# xv11_lidar_controller.net
KiCad netlist of a schematic drawn in EAGLE
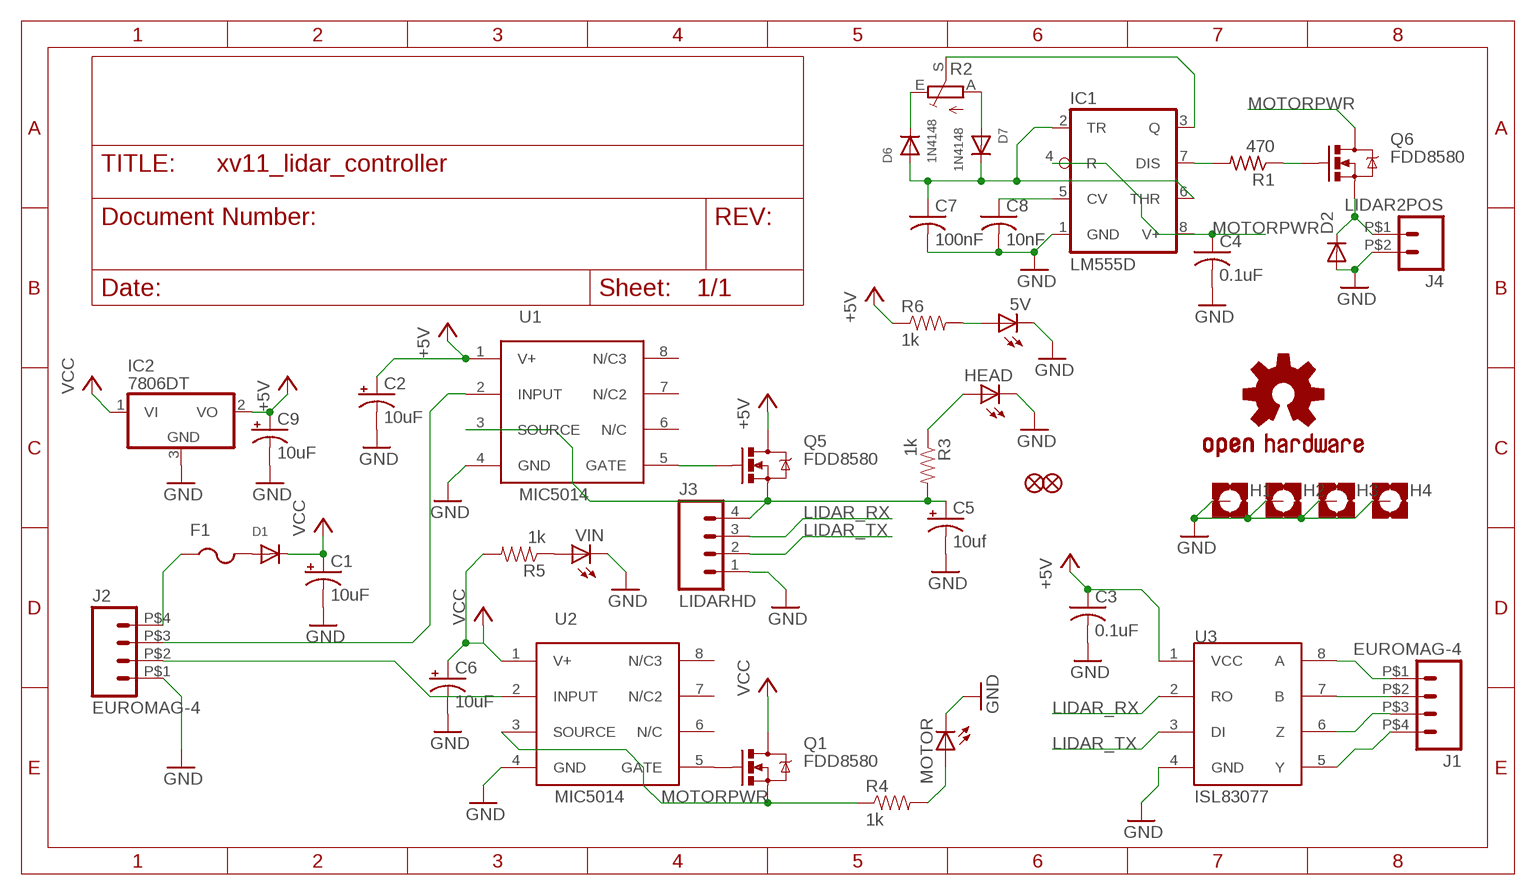
[diagram p0: schematic, sheet 1]

(export (version "E")
  (design (tool "Eeschema 10.0.6"))
  (components
    (comp (ref "5V")
      (value "LEDCHIP-LED0805")
      (footprint "eagle-import:CHIP-LED0805")
      (libsource (lib "eagle-import") (part "LEDCHIP-LED0805"))
    )
    (comp (ref "C1")
      (value "10uF")
      (footprint "eagle-import:CT6032")
      (libsource (lib "eagle-import") (part "CPOL-USCT6032"))
    )
    (comp (ref "C2")
      (value "10uF")
      (footprint "eagle-import:CT6032")
      (libsource (lib "eagle-import") (part "CPOL-USCT6032"))
    )
    (comp (ref "C3")
      (value "0.1uF")
      (footprint "eagle-import:C0805")
      (libsource (lib "eagle-import") (part "C-USC0805"))
    )
    (comp (ref "C4")
      (value "0.1uF")
      (footprint "eagle-import:C0805")
      (libsource (lib "eagle-import") (part "C-USC0805"))
    )
    (comp (ref "C5")
      (value "10uf")
      (footprint "eagle-import:CT6032")
      (libsource (lib "eagle-import") (part "CPOL-USCT6032"))
    )
    (comp (ref "C6")
      (value "10uF")
      (footprint "eagle-import:CT6032")
      (libsource (lib "eagle-import") (part "CPOL-USCT6032"))
    )
    (comp (ref "C7")
      (value "100nF")
      (footprint "eagle-import:C0805")
      (libsource (lib "eagle-import") (part "C-USC0805"))
    )
    (comp (ref "C8")
      (value "10nF")
      (footprint "eagle-import:C0805")
      (libsource (lib "eagle-import") (part "C-USC0805"))
    )
    (comp (ref "C9")
      (value "10uF")
      (footprint "eagle-import:CT6032")
      (libsource (lib "eagle-import") (part "CPOL-USCT6032"))
    )
    (comp (ref "D1")
      (value "DIODESMA")
      (footprint "eagle-import:SMADIODE")
      (libsource (lib "eagle-import") (part "adafruit_DIODESMA"))
    )
    (comp (ref "D2")
      (value "DIODESMA")
      (footprint "eagle-import:SMA-DIODE")
      (libsource (lib "eagle-import") (part "DIODESMA"))
    )
    (comp (ref "D6")
      (value "1N4148")
      (footprint "eagle-import:SOD-323F")
      (libsource (lib "eagle-import") (part "DIODESOD-323F"))
    )
    (comp (ref "D7")
      (value "1N4148")
      (footprint "eagle-import:SOD-323F")
      (libsource (lib "eagle-import") (part "DIODESOD-323F"))
    )
    (comp (ref "F1")
      (value "PTCFUSE-1812")
      (footprint "eagle-import:1812")
      (libsource (lib "eagle-import") (part "PTCFUSE-1812"))
    )
    (comp (ref "H1")
      (value "MOUNT-PAD-SQUARE5.5")
      (footprint "eagle-import:5,5-PAD-SQUARE")
      (libsource (lib "eagle-import") (part "MOUNT-PAD-SQUARE5.5"))
    )
    (comp (ref "H2")
      (value "MOUNT-PAD-SQUARE5.5")
      (footprint "eagle-import:5,5-PAD-SQUARE")
      (libsource (lib "eagle-import") (part "MOUNT-PAD-SQUARE5.5"))
    )
    (comp (ref "H3")
      (value "MOUNT-PAD-SQUARE5.5")
      (footprint "eagle-import:5,5-PAD-SQUARE")
      (libsource (lib "eagle-import") (part "MOUNT-PAD-SQUARE5.5"))
    )
    (comp (ref "H4")
      (value "MOUNT-PAD-SQUARE5.5")
      (footprint "eagle-import:5,5-PAD-SQUARE")
      (libsource (lib "eagle-import") (part "MOUNT-PAD-SQUARE5.5"))
    )
    (comp (ref "HEAD")
      (value "LEDCHIP-LED0805")
      (footprint "eagle-import:CHIP-LED0805")
      (libsource (lib "eagle-import") (part "LEDCHIP-LED0805"))
    )
    (comp (ref "IC1")
      (value "LM555D")
      (footprint "eagle-import:SO08")
      (libsource (lib "eagle-import") (part "555DLM"))
    )
    (comp (ref "IC2")
      (value "7806DT")
      (footprint "eagle-import:TO252")
      (libsource (lib "eagle-import") (part "78DT06"))
    )
    (comp (ref "J1")
      (value "EUROMAG-4")
      (footprint "eagle-import:M4")
      (libsource (lib "eagle-import") (part "EUROMAG-4"))
    )
    (comp (ref "J2")
      (value "EUROMAG-4")
      (footprint "eagle-import:M4")
      (libsource (lib "eagle-import") (part "EUROMAG-4"))
    )
    (comp (ref "J3")
      (value "LIDARHD")
      (footprint "eagle-import:2MM4POS")
      (libsource (lib "eagle-import") (part "LIDAR4POS"))
    )
    (comp (ref "J4")
      (value "LIDAR2POS")
      (footprint "eagle-import:2MM2POS")
      (libsource (lib "eagle-import") (part "LIDAR2POS"))
    )
    (comp (ref "JP1")
      (value "FIDUCIAL1.5X3")
      (footprint "eagle-import:FIDUCIAL-1.5X3")
      (libsource (lib "eagle-import") (part "FIDUCIAL1.5X3"))
    )
    (comp (ref "JP2")
      (value "FIDUCIAL1.5X3")
      (footprint "eagle-import:FIDUCIAL-1.5X3")
      (libsource (lib "eagle-import") (part "FIDUCIAL1.5X3"))
    )
    (comp (ref "MOTOR")
      (value "LEDCHIP-LED0805")
      (footprint "eagle-import:CHIP-LED0805")
      (libsource (lib "eagle-import") (part "LEDCHIP-LED0805"))
    )
    (comp (ref "Q1")
      (value "FDD8580")
      (footprint "eagle-import:DPAK")
      (libsource (lib "eagle-import") (part "MOSFET-NCHANNELFDD8580"))
    )
    (comp (ref "Q5")
      (value "FDD8580")
      (footprint "eagle-import:DPAK")
      (libsource (lib "eagle-import") (part "MOSFET-NCHANNELFDD8580"))
    )
    (comp (ref "Q6")
      (value "FDD8580")
      (footprint "eagle-import:DPAK")
      (libsource (lib "eagle-import") (part "MOSFET-NCHANNELFDD8580"))
    )
    (comp (ref "R1")
      (value "470")
      (footprint "eagle-import:R0805")
      (libsource (lib "eagle-import") (part "R-US_R0805"))
    )
    (comp (ref "R2")
      (value "TRIM_EU-B25P")
      (footprint "eagle-import:B25P")
      (libsource (lib "eagle-import") (part "TRIM_EU-B25P"))
    )
    (comp (ref "R3")
      (value "1k")
      (footprint "eagle-import:0805")
      (libsource (lib "eagle-import") (part "RESISTOR0805-RES"))
    )
    (comp (ref "R4")
      (value "1k")
      (footprint "eagle-import:0805")
      (libsource (lib "eagle-import") (part "RESISTOR0805-RES"))
    )
    (comp (ref "R5")
      (value "1k")
      (footprint "eagle-import:0805")
      (libsource (lib "eagle-import") (part "RESISTOR0805-RES"))
    )
    (comp (ref "R6")
      (value "1k")
      (footprint "eagle-import:0805")
      (libsource (lib "eagle-import") (part "RESISTOR0805-RES"))
    )
    (comp (ref "U$2")
      (value "OSHW-LOGOL")
      (footprint "eagle-import:OSHW-LOGO-L")
      (libsource (lib "eagle-import") (part "OSHW-LOGOL"))
    )
    (comp (ref "U1")
      (value "MIC5014")
      (footprint "eagle-import:SO08")
      (libsource (lib "eagle-import") (part "MIC5014"))
    )
    (comp (ref "U2")
      (value "MIC5014")
      (footprint "eagle-import:SO08")
      (libsource (lib "eagle-import") (part "MIC5014"))
    )
    (comp (ref "U3")
      (value "ISL83077")
      (footprint "eagle-import:SO08")
      (libsource (lib "eagle-import") (part "ISL83077"))
    )
    (comp (ref "VIN")
      (value "LEDCHIP-LED0805")
      (footprint "eagle-import:CHIP-LED0805")
      (libsource (lib "eagle-import") (part "LEDCHIP-LED0805"))
    )
  )
  (nets
    (net (code "1") (name "+5V") (class "Default")
      (node (ref "C2") (pin "+") (pinfunction "+_+") (pintype "passive"))
      (node (ref "C3") (pin "1") (pinfunction "1_1") (pintype "passive"))
      (node (ref "C9") (pin "+") (pinfunction "+_+") (pintype "passive"))
      (node (ref "IC2") (pin "2") (pinfunction "VO_2") (pintype "passive"))
      (node (ref "Q5") (pin "4") (pinfunction "D_4") (pintype "passive"))
      (node (ref "R6") (pin "1") (pinfunction "1_1") (pintype "passive"))
      (node (ref "U1") (pin "1") (pinfunction "V+_1") (pintype "bidirectional"))
      (node (ref "U3") (pin "1") (pinfunction "VCC_1") (pintype "bidirectional"))
    )
    (net (code "2") (name "/LIDAR_RX") (class "Default")
      (node (ref "J3") (pin "3") (pinfunction "3_3") (pintype "passive"))
      (node (ref "U3") (pin "2") (pinfunction "RO_2") (pintype "bidirectional"))
    )
    (net (code "3") (name "/LIDAR_TX") (class "Default")
      (node (ref "J3") (pin "2") (pinfunction "2_2") (pintype "passive"))
      (node (ref "U3") (pin "3") (pinfunction "DI_3") (pintype "bidirectional"))
    )
    (net (code "4") (name "/MOTORPWR") (class "Default")
      (node (ref "C4") (pin "1") (pinfunction "1_1") (pintype "passive"))
      (node (ref "IC1") (pin "4") (pinfunction "R_4") (pintype "input"))
      (node (ref "IC1") (pin "8") (pinfunction "V+_8") (pintype "power_in"))
      (node (ref "Q1") (pin "3") (pinfunction "S_3") (pintype "passive"))
      (node (ref "Q6") (pin "4") (pinfunction "D_4") (pintype "passive"))
      (node (ref "R4") (pin "1") (pinfunction "1_1") (pintype "passive"))
      (node (ref "U2") (pin "3") (pinfunction "SOURCE_3") (pintype "bidirectional"))
    )
    (net (code "5") (name "GND") (class "Default")
      (node (ref "5V") (pin "C") (pinfunction "C_C") (pintype "passive"))
      (node (ref "C1") (pin "-") (pinfunction "-_-") (pintype "passive"))
      (node (ref "C2") (pin "-") (pinfunction "-_-") (pintype "passive"))
      (node (ref "C3") (pin "2") (pinfunction "2_2") (pintype "passive"))
      (node (ref "C4") (pin "2") (pinfunction "2_2") (pintype "passive"))
      (node (ref "C5") (pin "-") (pinfunction "-_-") (pintype "passive"))
      (node (ref "C6") (pin "-") (pinfunction "-_-") (pintype "passive"))
      (node (ref "C7") (pin "2") (pinfunction "2_2") (pintype "passive"))
      (node (ref "C8") (pin "2") (pinfunction "2_2") (pintype "passive"))
      (node (ref "C9") (pin "-") (pinfunction "-_-") (pintype "passive"))
      (node (ref "D2") (pin "A") (pinfunction "A_A") (pintype "passive"))
      (node (ref "H1") (pin "B5,5") (pinfunction "MOUNT_B5,5") (pintype "passive"))
      (node (ref "H2") (pin "B5,5") (pinfunction "MOUNT_B5,5") (pintype "passive"))
      (node (ref "H3") (pin "B5,5") (pinfunction "MOUNT_B5,5") (pintype "passive"))
      (node (ref "H4") (pin "B5,5") (pinfunction "MOUNT_B5,5") (pintype "passive"))
      (node (ref "HEAD") (pin "C") (pinfunction "C_C") (pintype "passive"))
      (node (ref "IC1") (pin "1") (pinfunction "GND_1") (pintype "power_in"))
      (node (ref "IC2") (pin "3") (pinfunction "GND_3") (pintype "passive"))
      (node (ref "J2") (pin "P$1") (pinfunction "1_P$1") (pintype "passive"))
      (node (ref "J3") (pin "1") (pinfunction "1_1") (pintype "passive"))
      (node (ref "J4") (pin "P$2") (pinfunction "2_P$2") (pintype "passive"))
      (node (ref "MOTOR") (pin "C") (pinfunction "C_C") (pintype "passive"))
      (node (ref "U1") (pin "4") (pinfunction "GND_4") (pintype "bidirectional"))
      (node (ref "U2") (pin "4") (pinfunction "GND_4") (pintype "bidirectional"))
      (node (ref "U3") (pin "4") (pinfunction "GND_4") (pintype "bidirectional"))
      (node (ref "VIN") (pin "C") (pinfunction "C_C") (pintype "passive"))
    )
    (net (code "6") (name "Net-(5V-PadA)") (class "Default")
      (node (ref "5V") (pin "A") (pinfunction "A_A") (pintype "passive"))
      (node (ref "R6") (pin "2") (pinfunction "2_2") (pintype "passive"))
    )
    (net (code "7") (name "Net-(D1-PadA)") (class "Default")
      (node (ref "D1") (pin "A") (pinfunction "A_A") (pintype "passive"))
      (node (ref "F1") (pin "2") (pinfunction "2_2") (pintype "passive"))
    )
    (net (code "8") (name "Net-(D6-PadC)") (class "Default")
      (node (ref "D6") (pin "C") (pinfunction "C_C") (pintype "passive"))
      (node (ref "R2") (pin "E") (pinfunction "E_E") (pintype "passive"))
    )
    (net (code "9") (name "Net-(D7-PadA)") (class "Default")
      (node (ref "D7") (pin "A") (pinfunction "A_A") (pintype "passive"))
      (node (ref "R2") (pin "A") (pinfunction "A_A") (pintype "passive"))
    )
    (net (code "10") (name "Net-(HEAD-PadA)") (class "Default")
      (node (ref "HEAD") (pin "A") (pinfunction "A_A") (pintype "passive"))
      (node (ref "R3") (pin "1") (pinfunction "1_1") (pintype "passive"))
    )
    (net (code "11") (name "Net-(IC1-CV)") (class "Default")
      (node (ref "C8") (pin "1") (pinfunction "1_1") (pintype "passive"))
      (node (ref "IC1") (pin "5") (pinfunction "CV_5") (pintype "input"))
    )
    (net (code "12") (name "Net-(IC1-DIS)") (class "Default")
      (node (ref "IC1") (pin "7") (pinfunction "DIS_7") (pintype "input"))
      (node (ref "R1") (pin "2") (pinfunction "2_2") (pintype "passive"))
    )
    (net (code "13") (name "Net-(IC1-Q)") (class "Default")
      (node (ref "IC1") (pin "3") (pinfunction "Q_3") (pintype "output"))
      (node (ref "R2") (pin "S") (pinfunction "S_S") (pintype "passive"))
    )
    (net (code "14") (name "Net-(IC1-THR)") (class "Default")
      (node (ref "C7") (pin "1") (pinfunction "1_1") (pintype "passive"))
      (node (ref "D6") (pin "A") (pinfunction "A_A") (pintype "passive"))
      (node (ref "D7") (pin "C") (pinfunction "C_C") (pintype "passive"))
      (node (ref "IC1") (pin "2") (pinfunction "TR_2") (pintype "input"))
      (node (ref "IC1") (pin "6") (pinfunction "THR_6") (pintype "input"))
    )
    (net (code "15") (name "Net-(J1-1)") (class "Default")
      (node (ref "J1") (pin "P$1") (pinfunction "1_P$1") (pintype "passive"))
      (node (ref "U3") (pin "8") (pinfunction "A_8") (pintype "bidirectional"))
    )
    (net (code "16") (name "Net-(J1-2)") (class "Default")
      (node (ref "J1") (pin "P$2") (pinfunction "2_P$2") (pintype "passive"))
      (node (ref "U3") (pin "7") (pinfunction "B_7") (pintype "bidirectional"))
    )
    (net (code "17") (name "Net-(J1-3)") (class "Default")
      (node (ref "J1") (pin "P$3") (pinfunction "3_P$3") (pintype "passive"))
      (node (ref "U3") (pin "6") (pinfunction "Z_6") (pintype "bidirectional"))
    )
    (net (code "18") (name "Net-(J1-4)") (class "Default")
      (node (ref "J1") (pin "P$4") (pinfunction "4_P$4") (pintype "passive"))
      (node (ref "U3") (pin "5") (pinfunction "Y_5") (pintype "bidirectional"))
    )
    (net (code "19") (name "Net-(J2-2)") (class "Default")
      (node (ref "J2") (pin "P$2") (pinfunction "2_P$2") (pintype "passive"))
      (node (ref "U2") (pin "2") (pinfunction "INPUT_2") (pintype "bidirectional"))
    )
    (net (code "20") (name "Net-(J2-3)") (class "Default")
      (node (ref "J2") (pin "P$3") (pinfunction "3_P$3") (pintype "passive"))
      (node (ref "U1") (pin "2") (pinfunction "INPUT_2") (pintype "bidirectional"))
    )
    (net (code "21") (name "Net-(J2-4)") (class "Default")
      (node (ref "F1") (pin "1") (pinfunction "1_1") (pintype "passive"))
      (node (ref "J2") (pin "P$4") (pinfunction "4_P$4") (pintype "passive"))
    )
    (net (code "22") (name "Net-(J4-1)") (class "Default")
      (node (ref "D2") (pin "C") (pinfunction "C_C") (pintype "passive"))
      (node (ref "J4") (pin "P$1") (pinfunction "1_P$1") (pintype "passive"))
      (node (ref "Q6") (pin "3") (pinfunction "S_3") (pintype "passive"))
    )
    (net (code "23") (name "Net-(MOTOR-PadA)") (class "Default")
      (node (ref "MOTOR") (pin "A") (pinfunction "A_A") (pintype "passive"))
      (node (ref "R4") (pin "2") (pinfunction "2_2") (pintype "passive"))
    )
    (net (code "24") (name "Net-(Q1-G)") (class "Default")
      (node (ref "Q1") (pin "1") (pinfunction "G_1") (pintype "passive"))
      (node (ref "U2") (pin "5") (pinfunction "GATE_5") (pintype "bidirectional"))
    )
    (net (code "25") (name "Net-(Q5-G)") (class "Default")
      (node (ref "Q5") (pin "1") (pinfunction "G_1") (pintype "passive"))
      (node (ref "U1") (pin "5") (pinfunction "GATE_5") (pintype "bidirectional"))
    )
    (net (code "26") (name "Net-(Q5-S)") (class "Default")
      (node (ref "C5") (pin "+") (pinfunction "+_+") (pintype "passive"))
      (node (ref "J3") (pin "4") (pinfunction "4_4") (pintype "passive"))
      (node (ref "Q5") (pin "3") (pinfunction "S_3") (pintype "passive"))
      (node (ref "R3") (pin "2") (pinfunction "2_2") (pintype "passive"))
      (node (ref "U1") (pin "3") (pinfunction "SOURCE_3") (pintype "bidirectional"))
    )
    (net (code "27") (name "Net-(Q6-G)") (class "Default")
      (node (ref "Q6") (pin "1") (pinfunction "G_1") (pintype "passive"))
      (node (ref "R1") (pin "1") (pinfunction "1_1") (pintype "passive"))
    )
    (net (code "28") (name "Net-(R5-Pad1)") (class "Default")
      (node (ref "R5") (pin "1") (pinfunction "1_1") (pintype "passive"))
      (node (ref "VIN") (pin "A") (pinfunction "A_A") (pintype "passive"))
    )
    (net (code "29") (name "VCC") (class "Default")
      (node (ref "C1") (pin "+") (pinfunction "+_+") (pintype "passive"))
      (node (ref "C6") (pin "+") (pinfunction "+_+") (pintype "passive"))
      (node (ref "D1") (pin "C") (pinfunction "C_C") (pintype "passive"))
      (node (ref "IC2") (pin "1") (pinfunction "VI_1") (pintype "input"))
      (node (ref "Q1") (pin "4") (pinfunction "D_4") (pintype "passive"))
      (node (ref "R5") (pin "2") (pinfunction "2_2") (pintype "passive"))
      (node (ref "U2") (pin "1") (pinfunction "V+_1") (pintype "bidirectional"))
    )
    (net (code "30") (name "unconnected-(U1-N{slash}C-Pad6)") (class "Default")
      (node (ref "U1") (pin "6") (pinfunction "N/C_6") (pintype "bidirectional"))
    )
    (net (code "31") (name "unconnected-(U1-N{slash}C2-Pad7)") (class "Default")
      (node (ref "U1") (pin "7") (pinfunction "N/C2_7") (pintype "bidirectional"))
    )
    (net (code "32") (name "unconnected-(U1-N{slash}C3-Pad8)") (class "Default")
      (node (ref "U1") (pin "8") (pinfunction "N/C3_8") (pintype "bidirectional"))
    )
    (net (code "33") (name "unconnected-(U2-N{slash}C-Pad6)") (class "Default")
      (node (ref "U2") (pin "6") (pinfunction "N/C_6") (pintype "bidirectional"))
    )
    (net (code "34") (name "unconnected-(U2-N{slash}C2-Pad7)") (class "Default")
      (node (ref "U2") (pin "7") (pinfunction "N/C2_7") (pintype "bidirectional"))
    )
    (net (code "35") (name "unconnected-(U2-N{slash}C3-Pad8)") (class "Default")
      (node (ref "U2") (pin "8") (pinfunction "N/C3_8") (pintype "bidirectional"))
    )
  )
)
